# photon_at7020_1_rf_test.net
KiCad netlist of a schematic drawn in EAGLE
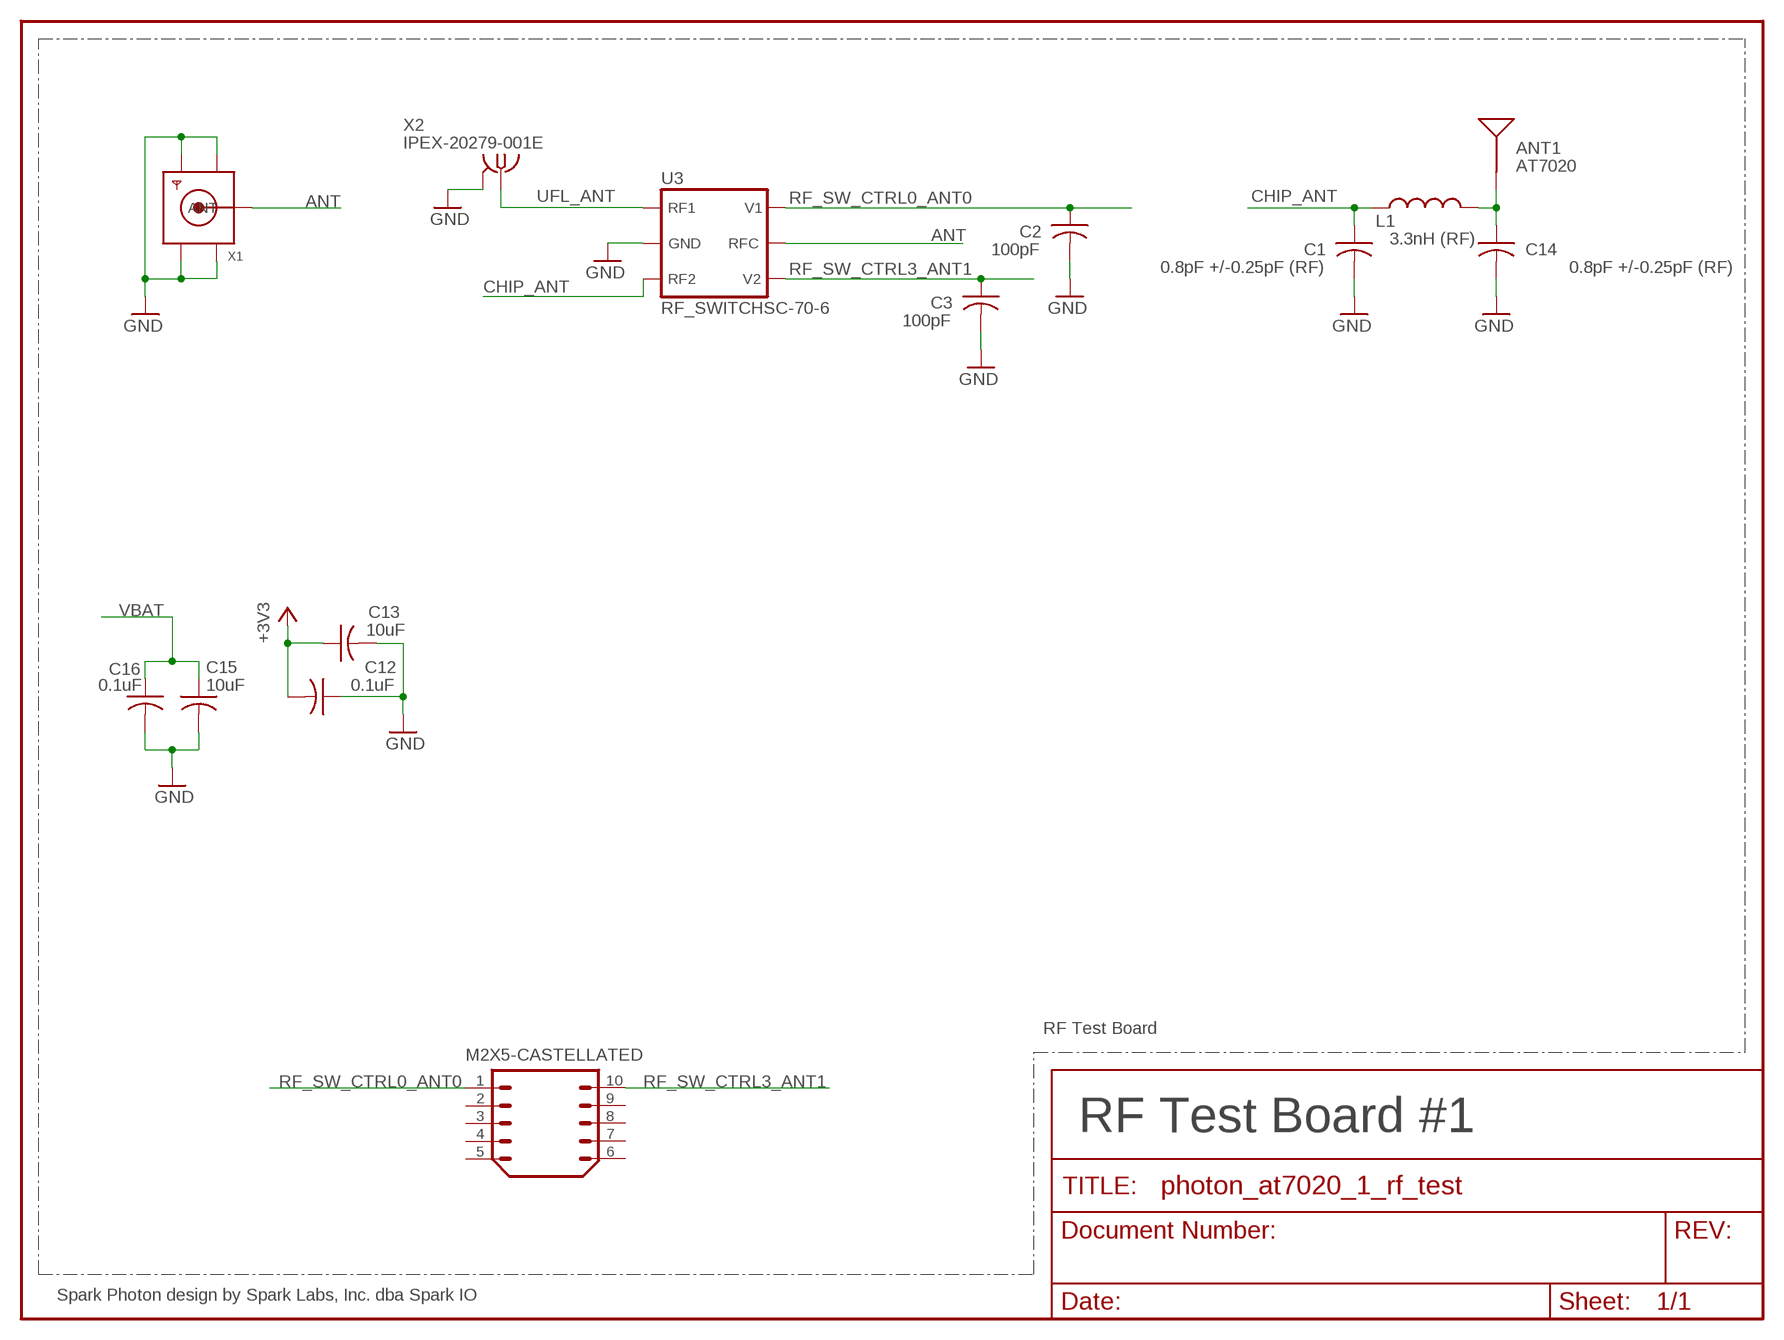
[diagram p0: schematic, sheet 1]

(export (version "E")
  (design (tool "Eeschema 10.0.6"))
  (components
    (comp (ref "ANT1")
      (value "AT7020")
      (footprint "eagle-import:AT7020")
      (libsource (lib "eagle-import") (part "AT7020"))
    )
    (comp (ref "C1")
      (value "0.8pF +/-0.25pF (RF)")
      (footprint "eagle-import:C0402_B")
      (libsource (lib "eagle-import") (part "C-US"))
    )
    (comp (ref "C2")
      (value "100pF")
      (footprint "eagle-import:C0402_B")
      (libsource (lib "eagle-import") (part "C-US"))
    )
    (comp (ref "C3")
      (value "100pF")
      (footprint "eagle-import:C0402_B")
      (libsource (lib "eagle-import") (part "C-US"))
    )
    (comp (ref "C12")
      (value "0.1uF")
      (footprint "eagle-import:C0402_B")
      (libsource (lib "eagle-import") (part "C-US"))
    )
    (comp (ref "C13")
      (value "10uF")
      (footprint "eagle-import:C0402_B")
      (libsource (lib "eagle-import") (part "C-US"))
    )
    (comp (ref "C14")
      (value "0.8pF +/-0.25pF (RF)")
      (footprint "eagle-import:C0402_B")
      (libsource (lib "eagle-import") (part "C-US"))
    )
    (comp (ref "C15")
      (value "10uF")
      (footprint "eagle-import:C0402_B")
      (libsource (lib "eagle-import") (part "C-US"))
    )
    (comp (ref "C16")
      (value "0.1uF")
      (footprint "eagle-import:C0402_B")
      (libsource (lib "eagle-import") (part "C-US"))
    )
    (comp (ref "L1")
      (value "3.3nH (RF)")
      (footprint "eagle-import:L0402_B")
      (libsource (lib "eagle-import") (part "INDUCTOR"))
    )
    (comp (ref "M2X5-CASTELLATED")
      (value "M2X5")
      (footprint "eagle-import:2X5-CASTELLATED")
      (libsource (lib "eagle-import") (part "M2X5"))
    )
    (comp (ref "U3")
      (value "RF_SWITCHSC-70-6")
      (footprint "eagle-import:SC70-6")
      (libsource (lib "eagle-import") (part "RF_SWITCHSC-70-6"))
    )
    (comp (ref "X1")
      (value "SMACONNECTOR_EDGE")
      (footprint "eagle-import:SMA_EDGELAUNCH")
      (libsource (lib "eagle-import") (part "SMACONNECTOR_EDGE"))
    )
    (comp (ref "X2")
      (value "IPEX-20279-001E")
      (footprint "eagle-import:IPEX-20279-001E")
      (libsource (lib "eagle-import") (part "IPEX-20279-001E"))
    )
  )
  (nets
    (net (code "1") (name "+3V3") (class "Default")
      (node (ref "C12") (pin "2") (pinfunction "2_2") (pintype "passive"))
      (node (ref "C13") (pin "1") (pinfunction "1_1") (pintype "passive"))
    )
    (net (code "2") (name "/ANT") (class "Default")
      (node (ref "U3") (pin "5") (pinfunction "RFC_5") (pintype "input"))
      (node (ref "X1") (pin "P") (pinfunction "ANT_P") (pintype "bidirectional"))
    )
    (net (code "3") (name "/CHIP_ANT") (class "Default")
      (node (ref "C1") (pin "1") (pinfunction "1_1") (pintype "passive"))
      (node (ref "L1") (pin "1") (pinfunction "1_1") (pintype "passive"))
      (node (ref "U3") (pin "3") (pinfunction "RF2_3") (pintype "output"))
    )
    (net (code "4") (name "/RF_SW_CTRL0_ANT0") (class "Default")
      (node (ref "C2") (pin "1") (pinfunction "1_1") (pintype "passive"))
      (node (ref "M2X5-CASTELLATED") (pin "1") (pinfunction "1_1") (pintype "passive"))
      (node (ref "U3") (pin "6") (pinfunction "V1_6") (pintype "input"))
    )
    (net (code "5") (name "/RF_SW_CTRL3_ANT1") (class "Default")
      (node (ref "C3") (pin "1") (pinfunction "1_1") (pintype "passive"))
      (node (ref "M2X5-CASTELLATED") (pin "10") (pinfunction "10_10") (pintype "passive"))
      (node (ref "U3") (pin "4") (pinfunction "V2_4") (pintype "input"))
    )
    (net (code "6") (name "/UFL_ANT") (class "Default")
      (node (ref "U3") (pin "1") (pinfunction "RF1_1") (pintype "output"))
      (node (ref "X2") (pin "1") (pinfunction "1_1") (pintype "passive"))
    )
    (net (code "7") (name "/VBAT") (class "Default")
      (node (ref "C15") (pin "1") (pinfunction "1_1") (pintype "passive"))
      (node (ref "C16") (pin "1") (pinfunction "1_1") (pintype "passive"))
    )
    (net (code "8") (name "GND") (class "Default")
      (node (ref "C1") (pin "2") (pinfunction "2_2") (pintype "passive"))
      (node (ref "C12") (pin "1") (pinfunction "1_1") (pintype "passive"))
      (node (ref "C13") (pin "2") (pinfunction "2_2") (pintype "passive"))
      (node (ref "C14") (pin "2") (pinfunction "2_2") (pintype "passive"))
      (node (ref "C15") (pin "2") (pinfunction "2_2") (pintype "passive"))
      (node (ref "C16") (pin "2") (pinfunction "2_2") (pintype "passive"))
      (node (ref "C2") (pin "2") (pinfunction "2_2") (pintype "passive"))
      (node (ref "C3") (pin "2") (pinfunction "2_2") (pintype "passive"))
      (node (ref "U3") (pin "2") (pinfunction "GND_2") (pintype "power_in"))
      (node (ref "X1") (pin "GND@1") (pinfunction "GND4_GND@1") (pintype "power_in"))
      (node (ref "X1") (pin "GND@2") (pinfunction "GND3_GND@2") (pintype "power_in"))
      (node (ref "X1") (pin "GND@3") (pinfunction "GND2_GND@3") (pintype "power_in"))
      (node (ref "X1") (pin "GND@4") (pinfunction "GND1_GND@4") (pintype "power_in"))
      (node (ref "X2") (pin "2@1") (pinfunction "GND_2@1") (pintype "passive"))
      (node (ref "X2") (pin "2@2") (pinfunction "GND_2@2") (pintype "passive"))
    )
    (net (code "9") (name "Net-(ANT1-SIGNAL)") (class "Default")
      (node (ref "ANT1") (pin "1") (pinfunction "SIGNAL_1") (pintype "bidirectional"))
      (node (ref "C14") (pin "1") (pinfunction "1_1") (pintype "passive"))
      (node (ref "L1") (pin "2") (pinfunction "2_2") (pintype "passive"))
    )
    (net (code "10") (name "unconnected-(M2X5-CASTELLATED-Pad2)") (class "Default")
      (node (ref "M2X5-CASTELLATED") (pin "2") (pinfunction "2_2") (pintype "passive"))
    )
    (net (code "11") (name "unconnected-(M2X5-CASTELLATED-Pad3)") (class "Default")
      (node (ref "M2X5-CASTELLATED") (pin "3") (pinfunction "3_3") (pintype "passive"))
    )
    (net (code "12") (name "unconnected-(M2X5-CASTELLATED-Pad4)") (class "Default")
      (node (ref "M2X5-CASTELLATED") (pin "4") (pinfunction "4_4") (pintype "passive"))
    )
    (net (code "13") (name "unconnected-(M2X5-CASTELLATED-Pad5)") (class "Default")
      (node (ref "M2X5-CASTELLATED") (pin "5") (pinfunction "5_5") (pintype "passive"))
    )
    (net (code "14") (name "unconnected-(M2X5-CASTELLATED-Pad6)") (class "Default")
      (node (ref "M2X5-CASTELLATED") (pin "6") (pinfunction "6_6") (pintype "passive"))
    )
    (net (code "15") (name "unconnected-(M2X5-CASTELLATED-Pad7)") (class "Default")
      (node (ref "M2X5-CASTELLATED") (pin "7") (pinfunction "7_7") (pintype "passive"))
    )
    (net (code "16") (name "unconnected-(M2X5-CASTELLATED-Pad8)") (class "Default")
      (node (ref "M2X5-CASTELLATED") (pin "8") (pinfunction "8_8") (pintype "passive"))
    )
    (net (code "17") (name "unconnected-(M2X5-CASTELLATED-Pad9)") (class "Default")
      (node (ref "M2X5-CASTELLATED") (pin "9") (pinfunction "9_9") (pintype "passive"))
    )
  )
)
